# working.net
KiCad netlist of a schematic drawn in EAGLE
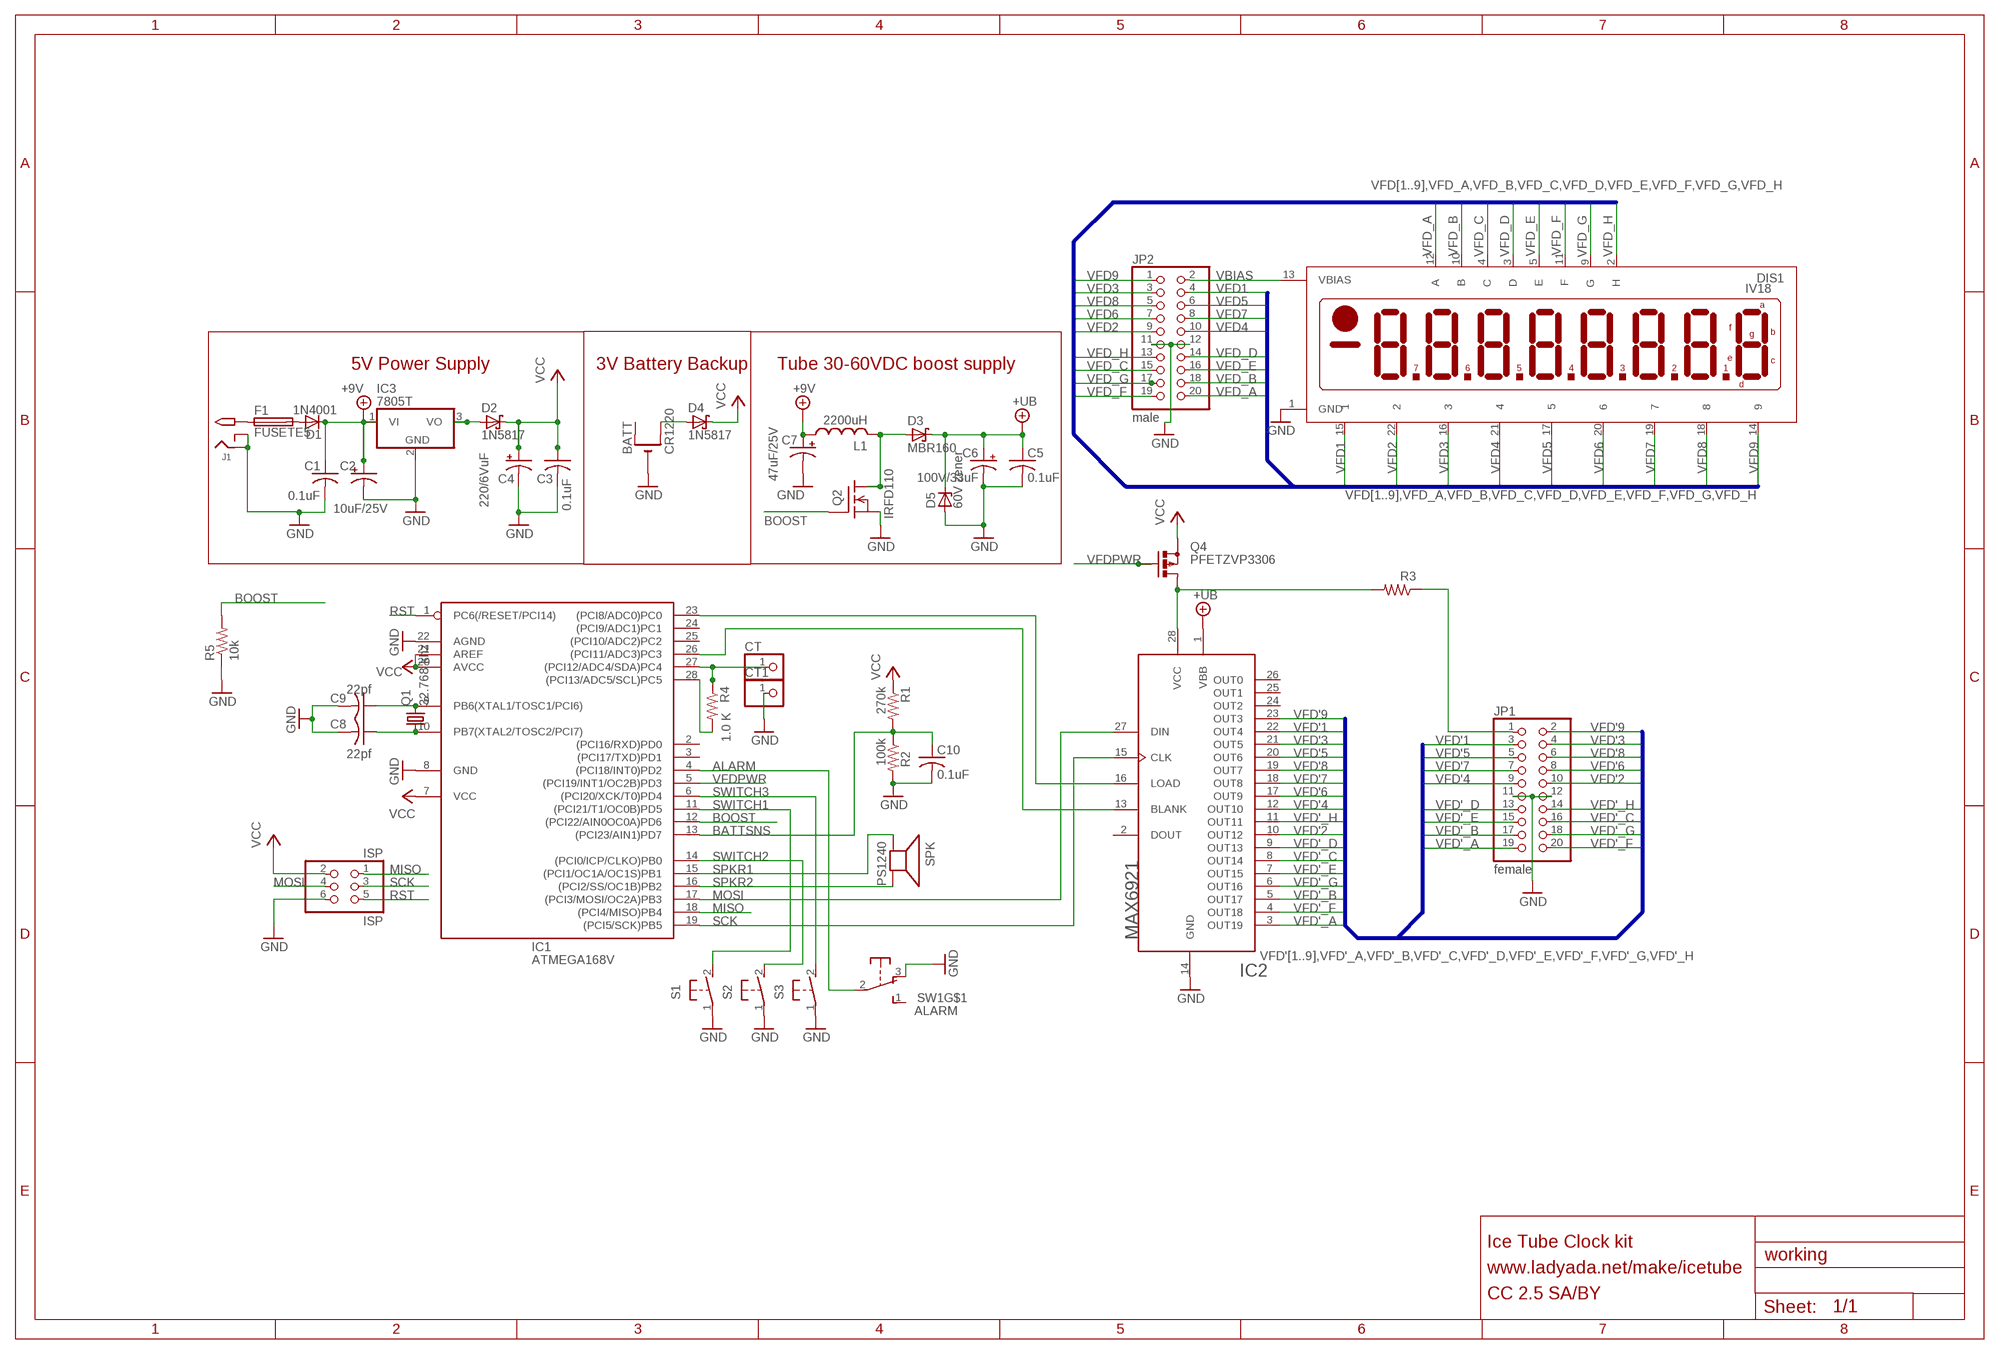
[diagram p0: schematic, sheet 1]

(export (version "E")
  (design (tool "Eeschema 10.0.6"))
  (components
    (comp (ref "BATT")
      (value "CR1220")
      (footprint "eagle-import:CR1220-THM")
      (libsource (lib "eagle-import") (part "CR1220THM"))
    )
    (comp (ref "C1")
      (value "0.1uF")
      (footprint "eagle-import:C025-025X050")
      (libsource (lib "eagle-import") (part "C-US025-025X050"))
    )
    (comp (ref "C2")
      (value "10uF/25V")
      (footprint "eagle-import:E2,5-6")
      (libsource (lib "eagle-import") (part "CPOL-USE2.5-6"))
    )
    (comp (ref "C3")
      (value "0.1uF")
      (footprint "eagle-import:C025-025X050")
      (libsource (lib "eagle-import") (part "C-US025-025X050"))
    )
    (comp (ref "C4")
      (value "220/6VuF")
      (footprint "eagle-import:E2,5-6")
      (libsource (lib "eagle-import") (part "CPOL-USE2.5-6"))
    )
    (comp (ref "C5")
      (value "0.1uF")
      (footprint "eagle-import:C025-024X044")
      (libsource (lib "eagle-import") (part "rcl-ez_C-US025-024X044"))
    )
    (comp (ref "C6")
      (value "100V/33uF")
      (footprint "eagle-import:E3,5-8")
      (libsource (lib "eagle-import") (part "rcl-ez_CPOL-USE3.5-8"))
    )
    (comp (ref "C7")
      (value "47uF/25V")
      (footprint "eagle-import:E2,5-6")
      (libsource (lib "eagle-import") (part "CPOL-USE2.5-6"))
    )
    (comp (ref "C8")
      (value "22pf")
      (footprint "eagle-import:C025-025X050")
      (libsource (lib "eagle-import") (part "C-US025-025X050"))
    )
    (comp (ref "C9")
      (value "22pf")
      (footprint "eagle-import:C025-025X050")
      (libsource (lib "eagle-import") (part "C-US025-025X050"))
    )
    (comp (ref "C10")
      (value "0.1uF")
      (footprint "eagle-import:C025-024X044")
      (libsource (lib "eagle-import") (part "rcl-ez_C-US025-024X044"))
    )
    (comp (ref "CT")
      (value "PINHD-1X1")
      (footprint "eagle-import:1X01")
      (libsource (lib "eagle-import") (part "PINHD-1X1"))
    )
    (comp (ref "CT1")
      (value "PINHD-1X1")
      (footprint "eagle-import:1X01")
      (libsource (lib "eagle-import") (part "PINHD-1X1"))
    )
    (comp (ref "D1")
      (value "1N4001")
      (footprint "eagle-import:DO41-10")
      (libsource (lib "eagle-import") (part "1N4004"))
    )
    (comp (ref "D2")
      (value "1N5817")
      (footprint "eagle-import:DO41-10")
      (libsource (lib "eagle-import") (part "SCHOTTKY-DIODEDO41"))
    )
    (comp (ref "D3")
      (value "MBR160")
      (footprint "eagle-import:DO41-10")
      (libsource (lib "eagle-import") (part "SCHOTTKY-DIODEDO41"))
    )
    (comp (ref "D4")
      (value "1N5817")
      (footprint "eagle-import:DO41-10")
      (libsource (lib "eagle-import") (part "SCHOTTKY-DIODEDO41"))
    )
    (comp (ref "D5")
      (value "60V zener")
      (footprint "eagle-import:DO41Z10")
      (libsource (lib "eagle-import") (part "ZENER-DIODEDO41Z10"))
    )
    (comp (ref "DIS1")
      (value "IV18")
      (footprint "eagle-import:IV18")
      (libsource (lib "eagle-import") (part "IV18"))
    )
    (comp (ref "F1")
      (value "FUSETE5")
      (footprint "eagle-import:TE5")
      (libsource (lib "eagle-import") (part "FUSETE5"))
    )
    (comp (ref "IC1")
      (value "ATMEGA168V")
      (footprint "eagle-import:DIL28_3")
      (libsource (lib "eagle-import") (part "ATMEGA168PROUND"))
    )
    (comp (ref "IC2")
      (value "MAX6921")
      (footprint "eagle-import:PLCC-S28")
      (libsource (lib "eagle-import") (part "MAX6921"))
    )
    (comp (ref "IC3")
      (value "7805T")
      (footprint "eagle-import:TO220H")
      (libsource (lib "eagle-import") (part "78T05"))
    )
    (comp (ref "ISP")
      (value "ISP")
      (footprint "eagle-import:2X03")
      (libsource (lib "eagle-import") (part "PINHD-2X3"))
    )
    (comp (ref "J1")
      (value "2.1MMJACK")
      (footprint "eagle-import:PJ-102A")
      (libsource (lib "eagle-import") (part "2.1MMJACK"))
    )
    (comp (ref "JP1")
      (value "female")
      (footprint "eagle-import:2X10")
      (libsource (lib "eagle-import") (part "PINHD-2X10"))
    )
    (comp (ref "JP2")
      (value "male")
      (footprint "eagle-import:2X10")
      (libsource (lib "eagle-import") (part "PINHD-2X10"))
    )
    (comp (ref "L1")
      (value "2200uH")
      (footprint "eagle-import:6000")
      (libsource (lib "eagle-import") (part "L"))
    )
    (comp (ref "Q1")
      (value "32.768 khz")
      (footprint "eagle-import:TC26V")
      (libsource (lib "eagle-import") (part "CRYTALTC26V"))
    )
    (comp (ref "Q2")
      (value "IRFD110")
      (footprint "eagle-import:DIL04")
      (libsource (lib "eagle-import") (part "IRFD110"))
    )
    (comp (ref "Q4")
      (value "PFETZVP3306")
      (footprint "eagle-import:TO92-OVAL")
      (libsource (lib "eagle-import") (part "PFETZVP3306"))
    )
    (comp (ref "R1")
      (value "270k")
      (footprint "eagle-import:0207_10")
      (libsource (lib "eagle-import") (part "R-US_0207/10"))
    )
    (comp (ref "R2")
      (value "100k")
      (footprint "eagle-import:0207_10")
      (libsource (lib "eagle-import") (part "R-US_0207/10"))
    )
    (comp (ref "R3")
      (value "22")
      (footprint "eagle-import:0207_10")
      (libsource (lib "eagle-import") (part "R-US_0207/10"))
    )
    (comp (ref "R4")
      (value "1.0 K")
      (footprint "eagle-import:0207_5V")
      (libsource (lib "eagle-import") (part "R-US_0207/5V"))
    )
    (comp (ref "R5")
      (value "10k")
      (footprint "eagle-import:0207_5V")
      (libsource (lib "eagle-import") (part "R-US_0207/5V"))
    )
    (comp (ref "S1")
      (value "31-XX")
      (footprint "eagle-import:B3F-31XX")
      (libsource (lib "eagle-import") (part "31-XX"))
    )
    (comp (ref "S2")
      (value "31-XX")
      (footprint "eagle-import:B3F-31XX")
      (libsource (lib "eagle-import") (part "31-XX"))
    )
    (comp (ref "S3")
      (value "31-XX")
      (footprint "eagle-import:B3F-31XX")
      (libsource (lib "eagle-import") (part "31-XX"))
    )
    (comp (ref "SPK")
      (value "PS1240")
      (footprint "eagle-import:PS12")
      (libsource (lib "eagle-import") (part "SPEAKER/PS12"))
    )
    (comp (ref "SW1")
      (value "ALARM")
      (footprint "eagle-import:OS102011MA1Q")
      (libsource (lib "eagle-import") (part "OS102011MA1Q"))
    )
  )
  (nets
    (net (code "1") (name "+9V") (class "Default")
      (node (ref "C1") (pin "1") (pinfunction "1_1") (pintype "passive"))
      (node (ref "C2") (pin "+") (pinfunction "+_+") (pintype "passive"))
      (node (ref "C7") (pin "+") (pinfunction "+_+") (pintype "passive"))
      (node (ref "D1") (pin "C") (pinfunction "C_C") (pintype "passive"))
      (node (ref "IC3") (pin "1") (pinfunction "VI_1") (pintype "input"))
      (node (ref "L1") (pin "1") (pinfunction "1_1") (pintype "passive"))
    )
    (net (code "2") (name "+UB") (class "Default")
      (node (ref "C5") (pin "1") (pinfunction "1_1") (pintype "passive"))
      (node (ref "C6") (pin "+") (pinfunction "+_+") (pintype "passive"))
      (node (ref "D3") (pin "C") (pinfunction "C_C") (pintype "passive"))
      (node (ref "D5") (pin "C") (pinfunction "C_C") (pintype "passive"))
      (node (ref "IC2") (pin "1") (pinfunction "VBB_1") (pintype "power_in"))
    )
    (net (code "3") (name "/ALARM") (class "Default")
      (node (ref "IC1") (pin "4") (pinfunction "(PCI18/INT0)PD2_4") (pintype "bidirectional"))
      (node (ref "SW1") (pin "2") (pinfunction "P_2") (pintype "passive"))
    )
    (net (code "4") (name "/BATTSNS") (class "Default")
      (node (ref "C10") (pin "1") (pinfunction "1_1") (pintype "passive"))
      (node (ref "IC1") (pin "13") (pinfunction "(PCI23/AIN1)PD7_13") (pintype "bidirectional"))
      (node (ref "R1") (pin "2") (pinfunction "2_2") (pintype "passive"))
      (node (ref "R2") (pin "1") (pinfunction "1_1") (pintype "passive"))
    )
    (net (code "5") (name "/BOOST") (class "Default")
      (node (ref "IC1") (pin "12") (pinfunction "(PCI22/AIN0OC0A)PD6_12") (pintype "bidirectional"))
      (node (ref "Q2") (pin "3") (pinfunction "G_3") (pintype "passive"))
      (node (ref "R5") (pin "2") (pinfunction "2_2") (pintype "passive"))
    )
    (net (code "6") (name "/MISO") (class "Default")
      (node (ref "IC1") (pin "18") (pinfunction "(PCI4/MISO)PB4_18") (pintype "bidirectional"))
      (node (ref "ISP") (pin "1") (pinfunction "1_1") (pintype "passive"))
    )
    (net (code "7") (name "/MOSI") (class "Default")
      (node (ref "IC1") (pin "17") (pinfunction "(PCI3/MOSI/OC2A)PB3_17") (pintype "bidirectional"))
      (node (ref "IC2") (pin "27") (pinfunction "DIN_27") (pintype "input"))
      (node (ref "ISP") (pin "4") (pinfunction "4_4") (pintype "passive"))
    )
    (net (code "8") (name "/RST") (class "Default")
      (node (ref "IC1") (pin "1") (pinfunction "PC6(/RESET/PCI14)_1") (pintype "bidirectional"))
      (node (ref "ISP") (pin "5") (pinfunction "5_5") (pintype "passive"))
    )
    (net (code "9") (name "/SCK") (class "Default")
      (node (ref "IC1") (pin "19") (pinfunction "(PCI5/SCK)PB5_19") (pintype "bidirectional"))
      (node (ref "IC2") (pin "15") (pinfunction "CLK_15") (pintype "input"))
      (node (ref "ISP") (pin "3") (pinfunction "3_3") (pintype "passive"))
    )
    (net (code "10") (name "/SPKR1") (class "Default")
      (node (ref "IC1") (pin "15") (pinfunction "(PCI1/OC1A/OC1S)PB1_15") (pintype "bidirectional"))
      (node (ref "SPK") (pin "P$1") (pinfunction "+_P$1") (pintype "passive"))
    )
    (net (code "11") (name "/SPKR2") (class "Default")
      (node (ref "IC1") (pin "16") (pinfunction "(PCI2/SS/OC1B)PB2_16") (pintype "bidirectional"))
      (node (ref "SPK") (pin "P$2") (pinfunction "-_P$2") (pintype "passive"))
    )
    (net (code "12") (name "/SWITCH1") (class "Default")
      (node (ref "IC1") (pin "11") (pinfunction "(PCI21/T1/OC0B)PD5_11") (pintype "bidirectional"))
      (node (ref "S1") (pin "2") (pinfunction "S_2") (pintype "passive"))
    )
    (net (code "13") (name "/SWITCH2") (class "Default")
      (node (ref "IC1") (pin "14") (pinfunction "(PCI0/ICP/CLKO)PB0_14") (pintype "bidirectional"))
      (node (ref "S2") (pin "2") (pinfunction "S_2") (pintype "passive"))
    )
    (net (code "14") (name "/SWITCH3") (class "Default")
      (node (ref "IC1") (pin "6") (pinfunction "(PCI20/XCK/T0)PD4_6") (pintype "bidirectional"))
      (node (ref "S3") (pin "2") (pinfunction "S_2") (pintype "passive"))
    )
    (net (code "15") (name "/VBIAS") (class "Default")
      (node (ref "DIS1") (pin "13") (pinfunction "VBIAS_13") (pintype "power_in"))
      (node (ref "JP2") (pin "2") (pinfunction "2_2") (pintype "passive"))
    )
    (net (code "16") (name "/VFD'1") (class "Default")
      (node (ref "IC2") (pin "22") (pinfunction "OUT4_22") (pintype "output"))
      (node (ref "JP1") (pin "3") (pinfunction "3_3") (pintype "passive"))
    )
    (net (code "17") (name "/VFD'2") (class "Default")
      (node (ref "IC2") (pin "10") (pinfunction "OUT12_10") (pintype "output"))
      (node (ref "JP1") (pin "10") (pinfunction "10_10") (pintype "passive"))
    )
    (net (code "18") (name "/VFD'3") (class "Default")
      (node (ref "IC2") (pin "21") (pinfunction "OUT5_21") (pintype "output"))
      (node (ref "JP1") (pin "4") (pinfunction "4_4") (pintype "passive"))
    )
    (net (code "19") (name "/VFD'4") (class "Default")
      (node (ref "IC2") (pin "12") (pinfunction "OUT10_12") (pintype "output"))
      (node (ref "JP1") (pin "9") (pinfunction "9_9") (pintype "passive"))
    )
    (net (code "20") (name "/VFD'5") (class "Default")
      (node (ref "IC2") (pin "20") (pinfunction "OUT6_20") (pintype "output"))
      (node (ref "JP1") (pin "5") (pinfunction "5_5") (pintype "passive"))
    )
    (net (code "21") (name "/VFD'6") (class "Default")
      (node (ref "IC2") (pin "17") (pinfunction "OUT9_17") (pintype "output"))
      (node (ref "JP1") (pin "8") (pinfunction "8_8") (pintype "passive"))
    )
    (net (code "22") (name "/VFD'7") (class "Default")
      (node (ref "IC2") (pin "18") (pinfunction "OUT8_18") (pintype "output"))
      (node (ref "JP1") (pin "7") (pinfunction "7_7") (pintype "passive"))
    )
    (net (code "23") (name "/VFD'8") (class "Default")
      (node (ref "IC2") (pin "19") (pinfunction "OUT7_19") (pintype "output"))
      (node (ref "JP1") (pin "6") (pinfunction "6_6") (pintype "passive"))
    )
    (net (code "24") (name "/VFD'9") (class "Default")
      (node (ref "IC2") (pin "23") (pinfunction "OUT3_23") (pintype "output"))
      (node (ref "JP1") (pin "2") (pinfunction "2_2") (pintype "passive"))
    )
    (net (code "25") (name "/VFD'_A") (class "Default")
      (node (ref "IC2") (pin "3") (pinfunction "OUT19_3") (pintype "output"))
      (node (ref "JP1") (pin "19") (pinfunction "19_19") (pintype "passive"))
    )
    (net (code "26") (name "/VFD'_B") (class "Default")
      (node (ref "IC2") (pin "5") (pinfunction "OUT17_5") (pintype "output"))
      (node (ref "JP1") (pin "17") (pinfunction "17_17") (pintype "passive"))
    )
    (net (code "27") (name "/VFD'_C") (class "Default")
      (node (ref "IC2") (pin "8") (pinfunction "OUT14_8") (pintype "output"))
      (node (ref "JP1") (pin "16") (pinfunction "16_16") (pintype "passive"))
    )
    (net (code "28") (name "/VFD'_D") (class "Default")
      (node (ref "IC2") (pin "9") (pinfunction "OUT13_9") (pintype "output"))
      (node (ref "JP1") (pin "13") (pinfunction "13_13") (pintype "passive"))
    )
    (net (code "29") (name "/VFD'_E") (class "Default")
      (node (ref "IC2") (pin "7") (pinfunction "OUT15_7") (pintype "output"))
      (node (ref "JP1") (pin "15") (pinfunction "15_15") (pintype "passive"))
    )
    (net (code "30") (name "/VFD'_F") (class "Default")
      (node (ref "IC2") (pin "4") (pinfunction "OUT18_4") (pintype "output"))
      (node (ref "JP1") (pin "20") (pinfunction "20_20") (pintype "passive"))
    )
    (net (code "31") (name "/VFD'_G") (class "Default")
      (node (ref "IC2") (pin "6") (pinfunction "OUT16_6") (pintype "output"))
      (node (ref "JP1") (pin "18") (pinfunction "18_18") (pintype "passive"))
    )
    (net (code "32") (name "/VFD'_H") (class "Default")
      (node (ref "IC2") (pin "11") (pinfunction "OUT11_11") (pintype "output"))
      (node (ref "JP1") (pin "14") (pinfunction "14_14") (pintype "passive"))
    )
    (net (code "33") (name "/VFD1") (class "Default")
      (node (ref "DIS1") (pin "15") (pinfunction "1_15") (pintype "passive"))
      (node (ref "JP2") (pin "4") (pinfunction "4_4") (pintype "passive"))
    )
    (net (code "34") (name "/VFD2") (class "Default")
      (node (ref "DIS1") (pin "22") (pinfunction "2_22") (pintype "passive"))
      (node (ref "JP2") (pin "9") (pinfunction "9_9") (pintype "passive"))
    )
    (net (code "35") (name "/VFD3") (class "Default")
      (node (ref "DIS1") (pin "16") (pinfunction "3_16") (pintype "passive"))
      (node (ref "JP2") (pin "3") (pinfunction "3_3") (pintype "passive"))
    )
    (net (code "36") (name "/VFD4") (class "Default")
      (node (ref "DIS1") (pin "21") (pinfunction "4_21") (pintype "passive"))
      (node (ref "JP2") (pin "10") (pinfunction "10_10") (pintype "passive"))
    )
    (net (code "37") (name "/VFD5") (class "Default")
      (node (ref "DIS1") (pin "17") (pinfunction "5_17") (pintype "passive"))
      (node (ref "JP2") (pin "6") (pinfunction "6_6") (pintype "passive"))
    )
    (net (code "38") (name "/VFD6") (class "Default")
      (node (ref "DIS1") (pin "20") (pinfunction "6_20") (pintype "passive"))
      (node (ref "JP2") (pin "7") (pinfunction "7_7") (pintype "passive"))
    )
    (net (code "39") (name "/VFD7") (class "Default")
      (node (ref "DIS1") (pin "19") (pinfunction "7_19") (pintype "passive"))
      (node (ref "JP2") (pin "8") (pinfunction "8_8") (pintype "passive"))
    )
    (net (code "40") (name "/VFD8") (class "Default")
      (node (ref "DIS1") (pin "18") (pinfunction "8_18") (pintype "passive"))
      (node (ref "JP2") (pin "5") (pinfunction "5_5") (pintype "passive"))
    )
    (net (code "41") (name "/VFD9") (class "Default")
      (node (ref "DIS1") (pin "14") (pinfunction "9_14") (pintype "passive"))
      (node (ref "JP2") (pin "1") (pinfunction "1_1") (pintype "passive"))
    )
    (net (code "42") (name "/VFDPWR") (class "Default")
      (node (ref "IC1") (pin "5") (pinfunction "(PCI19/INT1/OC2B)PD3_5") (pintype "bidirectional"))
      (node (ref "Q4") (pin "2") (pinfunction "G_2") (pintype "passive"))
    )
    (net (code "43") (name "/VFD_A") (class "Default")
      (node (ref "DIS1") (pin "12") (pinfunction "A_12") (pintype "passive"))
      (node (ref "JP2") (pin "20") (pinfunction "20_20") (pintype "passive"))
    )
    (net (code "44") (name "/VFD_B") (class "Default")
      (node (ref "DIS1") (pin "10") (pinfunction "B_10") (pintype "passive"))
      (node (ref "JP2") (pin "18") (pinfunction "18_18") (pintype "passive"))
    )
    (net (code "45") (name "/VFD_C") (class "Default")
      (node (ref "DIS1") (pin "4") (pinfunction "C_4") (pintype "passive"))
      (node (ref "JP2") (pin "15") (pinfunction "15_15") (pintype "passive"))
    )
    (net (code "46") (name "/VFD_D") (class "Default")
      (node (ref "DIS1") (pin "3") (pinfunction "D_3") (pintype "passive"))
      (node (ref "JP2") (pin "14") (pinfunction "14_14") (pintype "passive"))
    )
    (net (code "47") (name "/VFD_E") (class "Default")
      (node (ref "DIS1") (pin "5") (pinfunction "E_5") (pintype "passive"))
      (node (ref "JP2") (pin "16") (pinfunction "16_16") (pintype "passive"))
    )
    (net (code "48") (name "/VFD_F") (class "Default")
      (node (ref "DIS1") (pin "11") (pinfunction "F_11") (pintype "passive"))
      (node (ref "JP2") (pin "19") (pinfunction "19_19") (pintype "passive"))
    )
    (net (code "49") (name "/VFD_G") (class "Default")
      (node (ref "DIS1") (pin "9") (pinfunction "G_9") (pintype "passive"))
      (node (ref "JP2") (pin "17") (pinfunction "17_17") (pintype "passive"))
    )
    (net (code "50") (name "/VFD_H") (class "Default")
      (node (ref "DIS1") (pin "2") (pinfunction "H_2") (pintype "passive"))
      (node (ref "JP2") (pin "13") (pinfunction "13_13") (pintype "passive"))
    )
    (net (code "53") (name "GND") (class "Default")
      (node (ref "BATT") (pin "-") (pinfunction "-_-") (pintype "passive"))
      (node (ref "C1") (pin "2") (pinfunction "2_2") (pintype "passive"))
      (node (ref "C10") (pin "2") (pinfunction "2_2") (pintype "passive"))
      (node (ref "C2") (pin "-") (pinfunction "-_-") (pintype "passive"))
      (node (ref "C3") (pin "2") (pinfunction "2_2") (pintype "passive"))
      (node (ref "C4") (pin "-") (pinfunction "-_-") (pintype "passive"))
      (node (ref "C5") (pin "2") (pinfunction "2_2") (pintype "passive"))
      (node (ref "C6") (pin "-") (pinfunction "-_-") (pintype "passive"))
      (node (ref "C7") (pin "-") (pinfunction "-_-") (pintype "passive"))
      (node (ref "C8") (pin "2") (pinfunction "2_2") (pintype "passive"))
      (node (ref "C9") (pin "2") (pinfunction "2_2") (pintype "passive"))
      (node (ref "CT1") (pin "1") (pinfunction "1_1") (pintype "passive"))
      (node (ref "D5") (pin "A") (pinfunction "A_A") (pintype "passive"))
      (node (ref "DIS1") (pin "1") (pinfunction "GND_1") (pintype "power_in"))
      (node (ref "IC1") (pin "22") (pinfunction "AGND_22") (pintype "bidirectional"))
      (node (ref "IC1") (pin "8") (pinfunction "GND_8") (pintype "bidirectional"))
      (node (ref "IC2") (pin "14") (pinfunction "GND_14") (pintype "power_in"))
      (node (ref "IC3") (pin "2") (pinfunction "GND_2") (pintype "passive"))
      (node (ref "ISP") (pin "6") (pinfunction "6_6") (pintype "passive"))
      (node (ref "J1") (pin "RING") (pinfunction "RING_RING") (pintype "bidirectional"))
      (node (ref "J1") (pin "RING_SW") (pinfunction "RING_SW_RING_SW") (pintype "bidirectional"))
      (node (ref "JP1") (pin "11") (pinfunction "11_11") (pintype "passive"))
      (node (ref "JP1") (pin "12") (pinfunction "12_12") (pintype "passive"))
      (node (ref "JP2") (pin "11") (pinfunction "11_11") (pintype "passive"))
      (node (ref "JP2") (pin "12") (pinfunction "12_12") (pintype "passive"))
      (node (ref "Q2") (pin "4") (pinfunction "S_4") (pintype "passive"))
      (node (ref "R2") (pin "2") (pinfunction "2_2") (pintype "passive"))
      (node (ref "R5") (pin "1") (pinfunction "1_1") (pintype "passive"))
      (node (ref "S1") (pin "1") (pinfunction "P_1") (pintype "passive"))
      (node (ref "S2") (pin "1") (pinfunction "P_1") (pintype "passive"))
      (node (ref "S3") (pin "1") (pinfunction "P_1") (pintype "passive"))
      (node (ref "SW1") (pin "3") (pinfunction "O_3") (pintype "passive"))
    )
    (net (code "54") (name "Net-(BATT-+1)") (class "Default")
      (node (ref "BATT") (pin "+2") (pinfunction "+1_+2") (pintype "passive"))
      (node (ref "D4") (pin "A") (pinfunction "A_A") (pintype "passive"))
    )
    (net (code "55") (name "Net-(D1-PadA)") (class "Default")
      (node (ref "D1") (pin "A") (pinfunction "A_A") (pintype "passive"))
      (node (ref "F1") (pin "2") (pinfunction "2_2") (pintype "passive"))
    )
    (net (code "56") (name "Net-(F1-Pad1)") (class "Default")
      (node (ref "F1") (pin "1") (pinfunction "1_1") (pintype "passive"))
      (node (ref "J1") (pin "TIP") (pinfunction "TIP_TIP") (pintype "bidirectional"))
    )
    (net (code "57") (name "Net-(IC1-(PCI8{slash}ADC0)PC0)") (class "Default")
      (node (ref "IC1") (pin "23") (pinfunction "(PCI8/ADC0)PC0_23") (pintype "bidirectional"))
      (node (ref "IC2") (pin "16") (pinfunction "LOAD_16") (pintype "input"))
    )
    (net (code "58") (name "Net-(IC1-(PCI11{slash}ADC3)PC3)") (class "Default")
      (node (ref "IC1") (pin "26") (pinfunction "(PCI11/ADC3)PC3_26") (pintype "bidirectional"))
      (node (ref "IC2") (pin "13") (pinfunction "BLANK_13") (pintype "input"))
    )
    (net (code "59") (name "Net-(IC1-(PCI12{slash}ADC4{slash}SDA)PC4)") (class "Default")
      (node (ref "CT") (pin "1") (pinfunction "1_1") (pintype "passive"))
      (node (ref "IC1") (pin "27") (pinfunction "(PCI12/ADC4/SDA)PC4_27") (pintype "bidirectional"))
      (node (ref "R4") (pin "1") (pinfunction "1_1") (pintype "passive"))
    )
    (net (code "60") (name "Net-(IC1-(PCI13{slash}ADC5{slash}SCL)PC5)") (class "Default")
      (node (ref "IC1") (pin "28") (pinfunction "(PCI13/ADC5/SCL)PC5_28") (pintype "bidirectional"))
      (node (ref "R4") (pin "2") (pinfunction "2_2") (pintype "passive"))
    )
    (net (code "61") (name "Net-(IC1-PB6(XTAL1{slash}TOSC1{slash}PCI6))") (class "Default")
      (node (ref "C9") (pin "1") (pinfunction "1_1") (pintype "passive"))
      (node (ref "IC1") (pin "9") (pinfunction "PB6(XTAL1/TOSC1/PCI6)_9") (pintype "bidirectional"))
      (node (ref "Q1") (pin "2") (pinfunction "2_2") (pintype "passive"))
    )
    (net (code "62") (name "Net-(IC1-PB7(XTAL2{slash}TOSC2{slash}PCI7))") (class "Default")
      (node (ref "C8") (pin "1") (pinfunction "1_1") (pintype "passive"))
      (node (ref "IC1") (pin "10") (pinfunction "PB7(XTAL2/TOSC2/PCI7)_10") (pintype "bidirectional"))
      (node (ref "Q1") (pin "1") (pinfunction "1_1") (pintype "passive"))
    )
    (net (code "63") (name "Net-(IC2-VCC)") (class "Default")
      (node (ref "IC2") (pin "28") (pinfunction "VCC_28") (pintype "power_in"))
      (node (ref "Q4") (pin "3") (pinfunction "D_3") (pintype "passive"))
      (node (ref "R3") (pin "2") (pinfunction "2_2") (pintype "passive"))
    )
    (net (code "64") (name "Net-(IC3-VO)") (class "Default")
      (node (ref "D2") (pin "A") (pinfunction "A_A") (pintype "passive"))
      (node (ref "IC3") (pin "3") (pinfunction "VO_3") (pintype "passive"))
    )
    (net (code "65") (name "Net-(JP1-Pad1)") (class "Default")
      (node (ref "JP1") (pin "1") (pinfunction "1_1") (pintype "passive"))
      (node (ref "R3") (pin "1") (pinfunction "1_1") (pintype "passive"))
    )
    (net (code "66") (name "Net-(Q2-D)") (class "Default")
      (node (ref "D3") (pin "A") (pinfunction "A_A") (pintype "passive"))
      (node (ref "L1") (pin "2") (pinfunction "2_2") (pintype "passive"))
      (node (ref "Q2") (pin "1") (pinfunction "D_1") (pintype "passive"))
      (node (ref "Q2") (pin "2") (pinfunction "D1_2") (pintype "passive"))
    )
    (net (code "67") (name "VCC") (class "Default")
      (node (ref "C3") (pin "1") (pinfunction "1_1") (pintype "passive"))
      (node (ref "C4") (pin "+") (pinfunction "+_+") (pintype "passive"))
      (node (ref "D2") (pin "C") (pinfunction "C_C") (pintype "passive"))
      (node (ref "D4") (pin "C") (pinfunction "C_C") (pintype "passive"))
      (node (ref "IC1") (pin "20") (pinfunction "AVCC_20") (pintype "bidirectional"))
      (node (ref "IC1") (pin "21") (pinfunction "AREF_21") (pintype "bidirectional"))
      (node (ref "IC1") (pin "7") (pinfunction "VCC_7") (pintype "bidirectional"))
      (node (ref "ISP") (pin "2") (pinfunction "2_2") (pintype "passive"))
      (node (ref "Q4") (pin "1") (pinfunction "S_1") (pintype "passive"))
      (node (ref "R1") (pin "1") (pinfunction "1_1") (pintype "passive"))
    )
    (net (code "68") (name "unconnected-(BATT-+-Pad+1)") (class "Default")
      (node (ref "BATT") (pin "+1") (pinfunction "+_+1") (pintype "passive"))
    )
    (net (code "69") (name "unconnected-(IC1-(PCI9{slash}ADC1)PC1-Pad24)") (class "Default")
      (node (ref "IC1") (pin "24") (pinfunction "(PCI9/ADC1)PC1_24") (pintype "bidirectional"))
    )
    (net (code "70") (name "unconnected-(IC1-(PCI10{slash}ADC2)PC2-Pad25)") (class "Default")
      (node (ref "IC1") (pin "25") (pinfunction "(PCI10/ADC2)PC2_25") (pintype "bidirectional"))
    )
    (net (code "71") (name "unconnected-(IC1-(PCI16{slash}RXD)PD0-Pad2)") (class "Default")
      (node (ref "IC1") (pin "2") (pinfunction "(PCI16/RXD)PD0_2") (pintype "bidirectional"))
    )
    (net (code "72") (name "unconnected-(IC1-(PCI17{slash}TXD)PD1-Pad3)") (class "Default")
      (node (ref "IC1") (pin "3") (pinfunction "(PCI17/TXD)PD1_3") (pintype "bidirectional"))
    )
    (net (code "73") (name "unconnected-(IC2-DOUT-Pad2)") (class "Default")
      (node (ref "IC2") (pin "2") (pinfunction "DOUT_2") (pintype "output"))
    )
    (net (code "74") (name "unconnected-(IC2-OUT0-Pad26)") (class "Default")
      (node (ref "IC2") (pin "26") (pinfunction "OUT0_26") (pintype "output"))
    )
    (net (code "75") (name "unconnected-(IC2-OUT1-Pad25)") (class "Default")
      (node (ref "IC2") (pin "25") (pinfunction "OUT1_25") (pintype "output"))
    )
    (net (code "76") (name "unconnected-(IC2-OUT2-Pad24)") (class "Default")
      (node (ref "IC2") (pin "24") (pinfunction "OUT2_24") (pintype "output"))
    )
    (net (code "77") (name "unconnected-(SW1A-S-Pad1)") (class "Default")
      (node (ref "SW1") (pin "1") (pinfunction "S_1") (pintype "passive"))
    )
  )
)
